# board.net
KiCad netlist of a schematic drawn in EAGLE
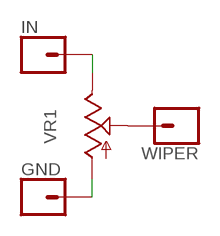
[diagram p0: schematic, sheet 1]

(export (version "E")
  (design (tool "Eeschema 10.0.6"))
  (components
    (comp (ref "GND")
      (value "CONN_01")
      (footprint "eagle-import:1X01")
      (libsource (lib "eagle-import") (part "CONN_01"))
    )
    (comp (ref "IN")
      (value "CONN_01")
      (footprint "eagle-import:1X01")
      (libsource (lib "eagle-import") (part "CONN_01"))
    )
    (comp (ref "VR1")
      (value "9MM_SNAP-IN_POT_")
      (footprint "eagle-import:9MM_SNAP-IN_POT")
      (libsource (lib "eagle-import") (part "9MM_SNAP-IN_POT_"))
    )
    (comp (ref "WIPER")
      (value "CONN_01")
      (footprint "eagle-import:1X01")
      (libsource (lib "eagle-import") (part "CONN_01"))
    )
  )
  (nets
    (net (code "1") (name "Net-(VR1-A)") (class "Default")
      (node (ref "GND") (pin "1") (pinfunction "1_1") (pintype "passive"))
      (node (ref "VR1") (pin "1") (pinfunction "A_1") (pintype "passive"))
    )
    (net (code "2") (name "Net-(VR1-E)") (class "Default")
      (node (ref "IN") (pin "1") (pinfunction "1_1") (pintype "passive"))
      (node (ref "VR1") (pin "3") (pinfunction "E_3") (pintype "passive"))
    )
    (net (code "3") (name "Net-(VR1-S)") (class "Default")
      (node (ref "VR1") (pin "2") (pinfunction "S_2") (pintype "passive"))
      (node (ref "WIPER") (pin "1") (pinfunction "1_1") (pintype "passive"))
    )
  )
)
